# MODULO_DRIVE_CC.net
KiCad netlist of a schematic drawn in EAGLE
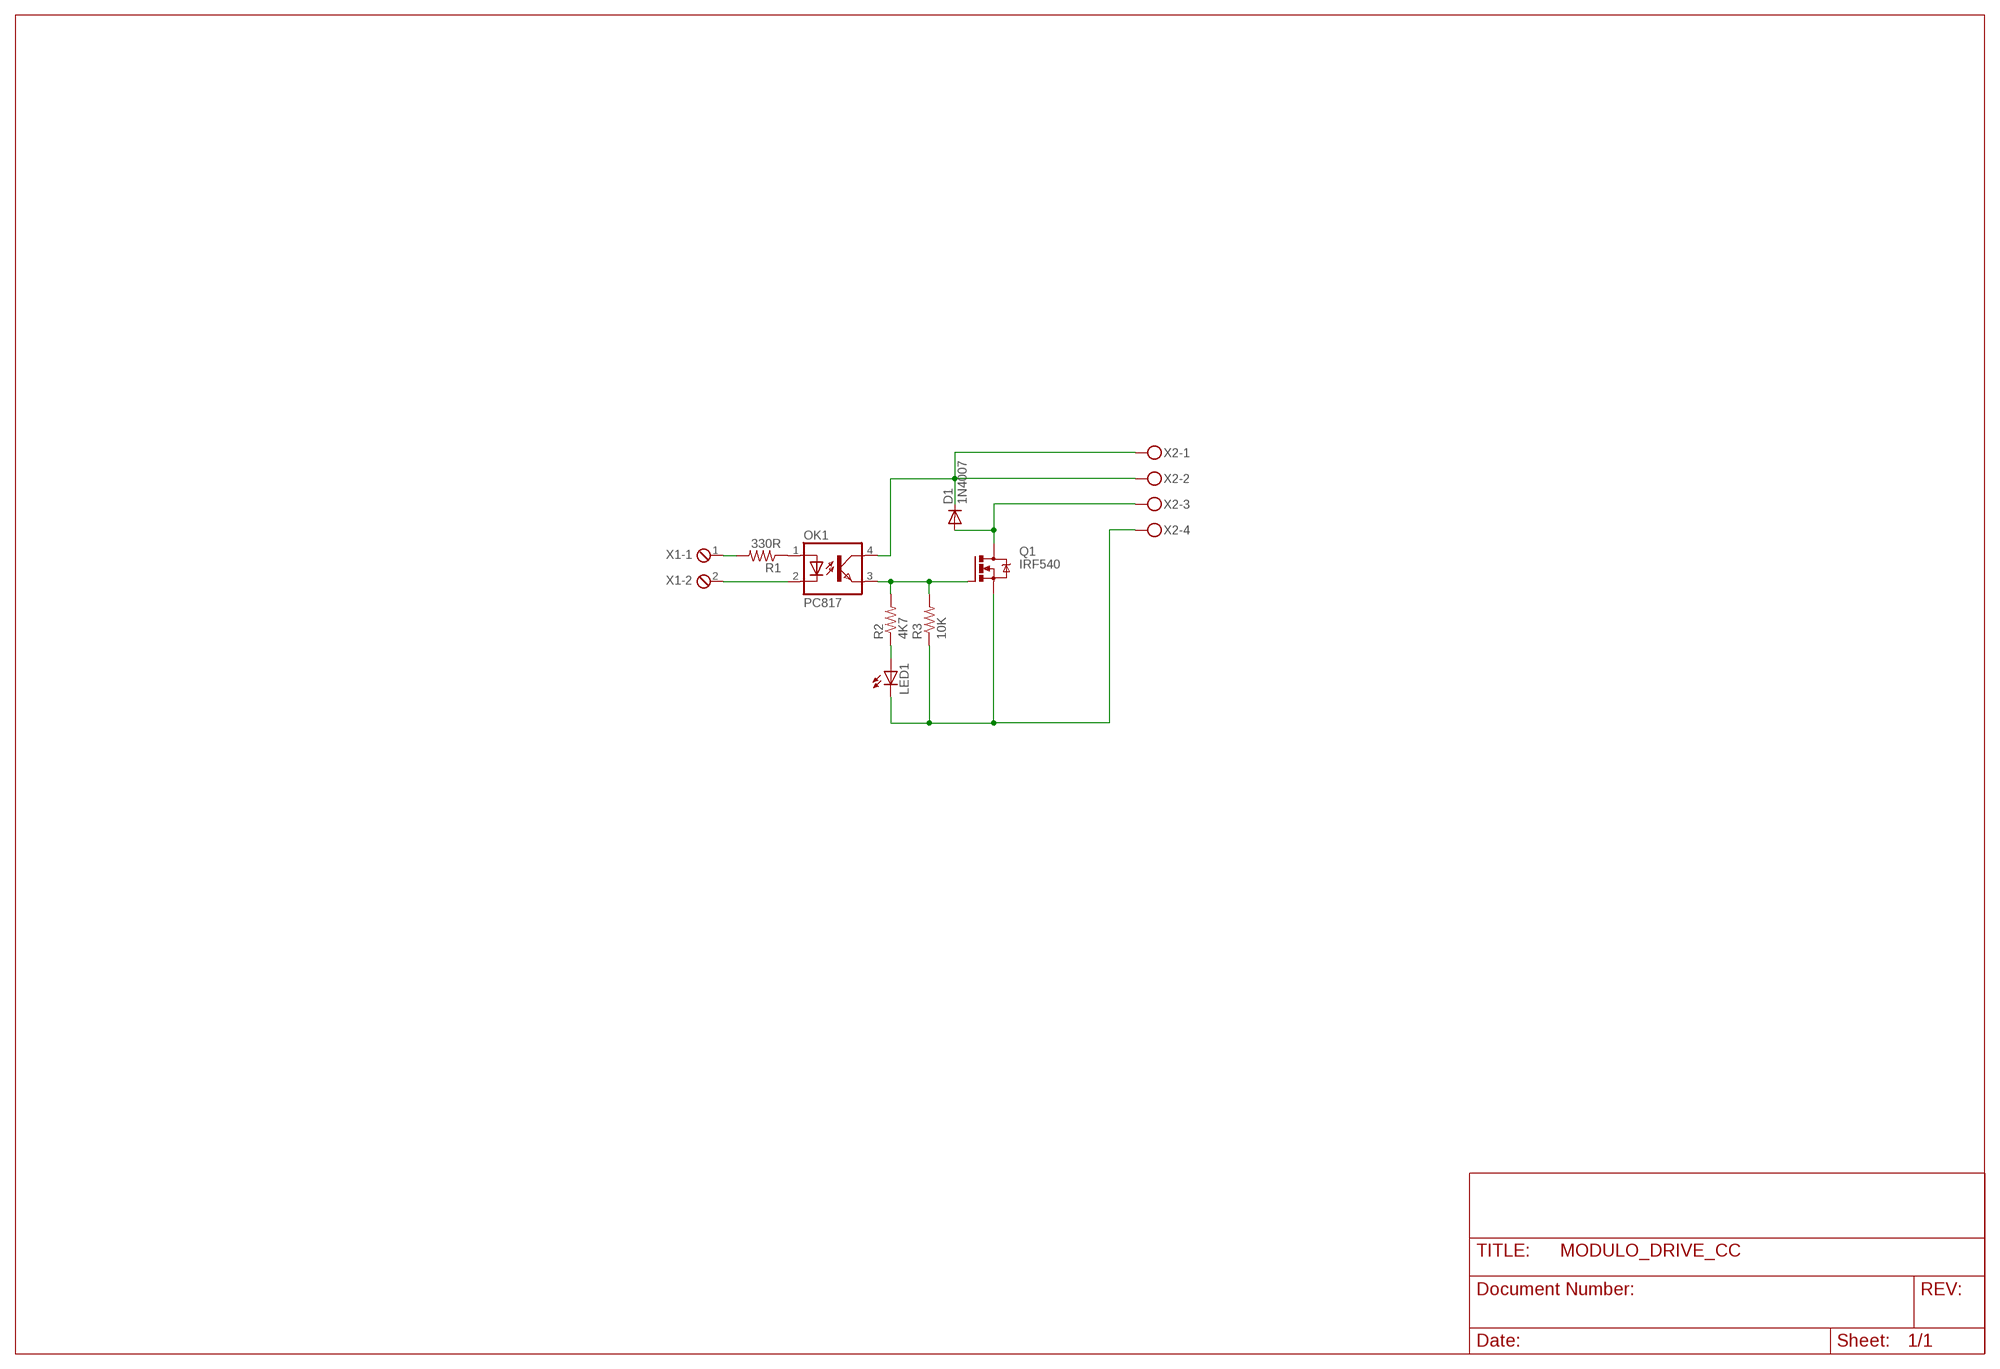
[diagram p0: schematic, sheet 1]

(export (version "E")
  (design (tool "Eeschema 10.0.6"))
  (components
    (comp (ref "D1")
      (value "1N4007")
      (footprint "eagle-import:DO41-10")
      (libsource (lib "eagle-import") (part "1N4004"))
    )
    (comp (ref "LED1")
      (value "LED3MM")
      (footprint "eagle-import:LED3MM")
      (libsource (lib "eagle-import") (part "LED3MM"))
    )
    (comp (ref "OK1")
      (value "PC817")
      (footprint "eagle-import:DIL04")
      (fields (field (name "MPN") "PC817X4J000F"))
      (libsource (lib "eagle-import") (part "PC817"))
    )
    (comp (ref "Q1")
      (value "IRF540")
      (footprint "eagle-import:TO220BV")
      (libsource (lib "eagle-import") (part "IRF540"))
    )
    (comp (ref "R1")
      (value "330R")
      (footprint "eagle-import:AXIAL-0.4")
      (libsource (lib "eagle-import") (part "RESISTORPTH-1/4W"))
    )
    (comp (ref "R2")
      (value "4K7")
      (footprint "eagle-import:AXIAL-0.4")
      (libsource (lib "eagle-import") (part "RESISTORPTH-1/4W"))
    )
    (comp (ref "R3")
      (value "10K")
      (footprint "eagle-import:AXIAL-0.4")
      (libsource (lib "eagle-import") (part "RESISTORPTH-1/4W"))
    )
    (comp (ref "X1")
      (value "MPT2")
      (footprint "eagle-import:2POL254")
      (libsource (lib "eagle-import") (part "MPT2"))
    )
    (comp (ref "X2")
      (value "MKDSN1,5/4-5,08")
      (footprint "eagle-import:MKDSN1,5_4-5,08")
      (fields (field (name "MPN") "SMKDSN1,5/4-5,08"))
      (libsource (lib "eagle-import") (part "MKDSN1,5/4-5,08"))
    )
  )
  (nets
    (net (code "1") (name "Net-(LED1-C)") (class "Default")
      (node (ref "LED1") (pin "K") (pinfunction "C_K") (pintype "passive"))
      (node (ref "Q1") (pin "S") (pinfunction "S_S") (pintype "passive"))
      (node (ref "R3") (pin "P$1") (pinfunction "1_P$1") (pintype "passive"))
      (node (ref "X2") (pin "4") (pinfunction "KL_4") (pintype "passive"))
    )
    (net (code "2") (name "Net-(OK1-A)") (class "Default")
      (node (ref "OK1") (pin "1") (pinfunction "A_1") (pintype "passive"))
      (node (ref "R1") (pin "P$1") (pinfunction "1_P$1") (pintype "passive"))
    )
    (net (code "3") (name "Net-(OK1-C)") (class "Default")
      (node (ref "OK1") (pin "2") (pinfunction "C_2") (pintype "passive"))
      (node (ref "X1") (pin "2") (pinfunction "1_2") (pintype "passive"))
    )
    (net (code "4") (name "Net-(OK1-COL)") (class "Default")
      (node (ref "D1") (pin "C") (pinfunction "C_C") (pintype "passive"))
      (node (ref "OK1") (pin "4") (pinfunction "COL_4") (pintype "passive"))
      (node (ref "X2") (pin "1") (pinfunction "KL_1") (pintype "passive"))
      (node (ref "X2") (pin "2") (pinfunction "KL_2") (pintype "passive"))
    )
    (net (code "5") (name "Net-(OK1-EMIT)") (class "Default")
      (node (ref "OK1") (pin "3") (pinfunction "EMIT_3") (pintype "passive"))
      (node (ref "Q1") (pin "G") (pinfunction "G_G") (pintype "passive"))
      (node (ref "R2") (pin "P$2") (pinfunction "2_P$2") (pintype "passive"))
      (node (ref "R3") (pin "P$2") (pinfunction "2_P$2") (pintype "passive"))
    )
    (net (code "6") (name "Net-(R1-2)") (class "Default")
      (node (ref "R1") (pin "P$2") (pinfunction "2_P$2") (pintype "passive"))
      (node (ref "X1") (pin "1") (pinfunction "1_1") (pintype "passive"))
    )
    (net (code "7") (name "Net-(R2-1)") (class "Default")
      (node (ref "LED1") (pin "A") (pinfunction "A_A") (pintype "passive"))
      (node (ref "R2") (pin "P$1") (pinfunction "1_P$1") (pintype "passive"))
    )
    (net (code "8") (name "Net-(X2C-KL)") (class "Default")
      (node (ref "D1") (pin "A") (pinfunction "A_A") (pintype "passive"))
      (node (ref "Q1") (pin "D") (pinfunction "D_D") (pintype "passive"))
      (node (ref "X2") (pin "3") (pinfunction "KL_3") (pintype "passive"))
    )
  )
)
